# 3.net
KiCad netlist of a schematic drawn in Altium Designer
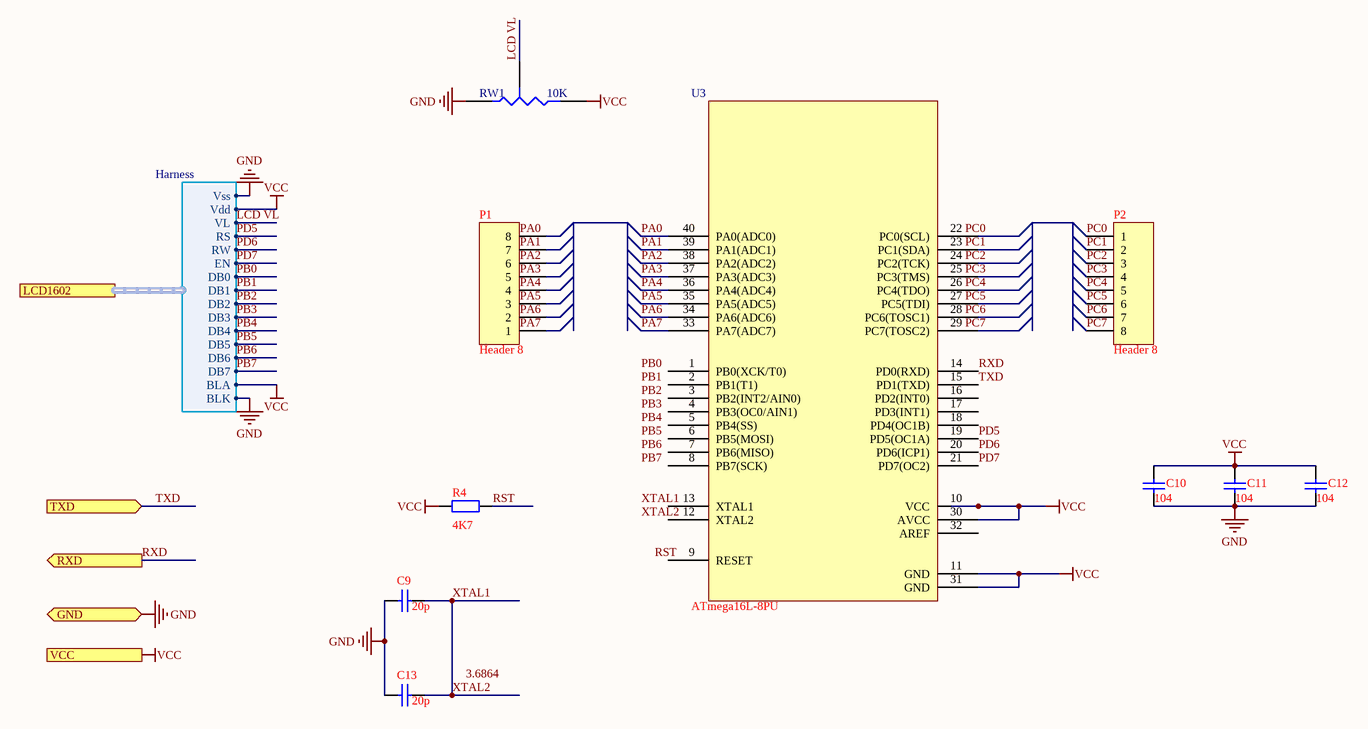
[diagram p0: 3.SchDoc]

(export (version "E")
  (design (tool "Eeschema 10.0.6"))
  (components
    (comp (ref "*") (value "ATmega16L-8PU") (libsource (lib "altium-import") (part "root_0_ATmega16L-8PU_")))
    (comp (ref "C9")
      (value "20p")
      (footprint "0402")
      (description "Capacitor (Semiconductor SIM Model)")
      (fields (field (name "Comment") "Cap Semi") (field (name "PUBLISHER") "Altium Limited"))
      (libsource (lib "Miscellaneous Devices") (part "Cap Semi"))
    )
    (comp (ref "C10")
      (value "104")
      (footprint "0402")
      (description "Capacitor (Semiconductor SIM Model)")
      (fields (field (name "Comment") "Cap Semi") (field (name "PUBLISHER") "Altium Limited"))
      (libsource (lib "Miscellaneous Devices") (part "Cap Semi"))
    )
    (comp (ref "C11")
      (value "104")
      (footprint "0402")
      (description "Capacitor (Semiconductor SIM Model)")
      (fields (field (name "Comment") "Cap Semi") (field (name "PUBLISHER") "Altium Limited"))
      (libsource (lib "Miscellaneous Devices") (part "Cap Semi"))
    )
    (comp (ref "C12")
      (value "104")
      (footprint "0402")
      (description "Capacitor (Semiconductor SIM Model)")
      (fields (field (name "Comment") "Cap Semi") (field (name "PUBLISHER") "Altium Limited"))
      (libsource (lib "Miscellaneous Devices") (part "Cap Semi"))
    )
    (comp (ref "C13")
      (value "20p")
      (footprint "0402")
      (description "Capacitor (Semiconductor SIM Model)")
      (fields (field (name "Comment") "Cap Semi") (field (name "PUBLISHER") "Altium Limited"))
      (libsource (lib "Miscellaneous Devices") (part "Cap Semi"))
    )
    (comp (ref "P1")
      (value "Header 8")
      (footprint "HDR1X8")
      (description "Header, 8-Pin")
      (fields (field (name "PUBLISHER") "Altium Limited"))
      (libsource (lib "") (part "Header 8_1"))
    )
    (comp (ref "P2")
      (value "Header 8")
      (footprint "HDR1X8")
      (description "Header, 8-Pin")
      (fields (field (name "PUBLISHER") "Altium Limited"))
      (libsource (lib "Miscellaneous Connectors") (part "Header 8"))
    )
    (comp (ref "R4")
      (value "4K7")
      (footprint "AXIAL-0.4")
      (description "Resistor")
      (fields (field (name "Comment") "Res2") (field (name "PUBLISHER") "Altium Limited"))
      (libsource (lib "Miscellaneous Devices") (part "Res2"))
    )
    (comp (ref "RW1")
      (value "10K")
      (footprint "VR3")
      (description "Tapped Resistor")
      (fields (field (name "Comment") "Res Tap") (field (name "PUBLISHER") "Altium Limited"))
      (libsource (lib "Miscellaneous Devices") (part "Res Tap"))
    )
    (comp (ref "U3") (value "ATmega16L-8PU") (libsource (lib "Schlib1") (part "ATmega16L-8PU")))
  )
  (nets
    (net (code "3") (name "/LCD VL") (class "Default")
      (node (ref "RW1") (pin "3") (pinfunction "TAP_3") (pintype "passive"))
    )
    (net (code "4") (name "/PA0") (class "Default")
      (node (ref "U3") (pin "40") (pinfunction "PA0(ADC0)_40") (pintype "passive"))
    )
    (net (code "5") (name "/PA1") (class "Default")
      (node (ref "U3") (pin "39") (pinfunction "PA1(ADC1)_39") (pintype "passive"))
    )
    (net (code "6") (name "/PA2") (class "Default")
      (node (ref "U3") (pin "38") (pinfunction "PA2(ADC2)_38") (pintype "passive"))
    )
    (net (code "7") (name "/PA3") (class "Default")
      (node (ref "U3") (pin "37") (pinfunction "PA3(ADC3)_37") (pintype "passive"))
    )
    (net (code "8") (name "/PA4") (class "Default")
      (node (ref "U3") (pin "36") (pinfunction "PA4(ADC4)_36") (pintype "passive"))
    )
    (net (code "9") (name "/PA5") (class "Default")
      (node (ref "U3") (pin "35") (pinfunction "PA5(ADC5)_35") (pintype "passive"))
    )
    (net (code "10") (name "/PA6") (class "Default")
      (node (ref "U3") (pin "34") (pinfunction "PA6(ADC6)_34") (pintype "passive"))
    )
    (net (code "11") (name "/PA7") (class "Default")
      (node (ref "U3") (pin "33") (pinfunction "PA7(ADC7)_33") (pintype "passive"))
    )
    (net (code "20") (name "/PC0") (class "Default")
      (node (ref "P2") (pin "1") (pinfunction "1_1") (pintype "passive"))
    )
    (net (code "21") (name "/PC1") (class "Default")
      (node (ref "P2") (pin "2") (pinfunction "2_2") (pintype "passive"))
    )
    (net (code "22") (name "/PC2") (class "Default")
      (node (ref "P2") (pin "3") (pinfunction "3_3") (pintype "passive"))
    )
    (net (code "23") (name "/PC3") (class "Default")
      (node (ref "P2") (pin "4") (pinfunction "4_4") (pintype "passive"))
    )
    (net (code "24") (name "/PC4") (class "Default")
      (node (ref "P2") (pin "5") (pinfunction "5_5") (pintype "passive"))
    )
    (net (code "25") (name "/PC5") (class "Default")
      (node (ref "P2") (pin "6") (pinfunction "6_6") (pintype "passive"))
    )
    (net (code "26") (name "/PC6") (class "Default")
      (node (ref "P2") (pin "7") (pinfunction "7_7") (pintype "passive"))
    )
    (net (code "27") (name "/PC7") (class "Default")
      (node (ref "P2") (pin "8") (pinfunction "8_8") (pintype "passive"))
    )
    (net (code "28") (name "/PD5") (class "Default")
      (node (ref "U3") (pin "19") (pinfunction "PD5(OC1A)_19") (pintype "passive"))
    )
    (net (code "29") (name "/PD6") (class "Default")
      (node (ref "U3") (pin "20") (pinfunction "PD6(ICP1)_20") (pintype "passive"))
    )
    (net (code "30") (name "/PD7") (class "Default")
      (node (ref "U3") (pin "21") (pinfunction "PD7(OC2)_21") (pintype "passive"))
    )
    (net (code "31") (name "/RST") (class "Default")
      (node (ref "R4") (pin "2") (pinfunction "2_2") (pintype "passive"))
    )
    (net (code "32") (name "/RXD") (class "Default")
      (node (ref "U3") (pin "14") (pinfunction "PD0(RXD)_14") (pintype "passive"))
    )
    (net (code "33") (name "/TXD") (class "Default")
      (node (ref "U3") (pin "15") (pinfunction "PD1(TXD)_15") (pintype "passive"))
    )
    (net (code "34") (name "/XTAL1") (class "Default")
      (node (ref "C13") (pin "2") (pinfunction "2_2") (pintype "passive"))
      (node (ref "C9") (pin "2") (pinfunction "2_2") (pintype "passive"))
    )
    (net (code "36") (name "GND") (class "Default")
      (node (ref "C10") (pin "2") (pinfunction "2_2") (pintype "passive"))
      (node (ref "C11") (pin "1") (pinfunction "1_1") (pintype "passive"))
      (node (ref "C12") (pin "1") (pinfunction "1_1") (pintype "passive"))
      (node (ref "C13") (pin "1") (pinfunction "1_1") (pintype "passive"))
      (node (ref "C9") (pin "1") (pinfunction "1_1") (pintype "passive"))
      (node (ref "RW1") (pin "1") (pinfunction "A_1") (pintype "passive"))
    )
    (net (code "37") (name "VCC") (class "Default")
      (node (ref "C10") (pin "1") (pinfunction "1_1") (pintype "passive"))
      (node (ref "C11") (pin "2") (pinfunction "2_2") (pintype "passive"))
      (node (ref "C12") (pin "2") (pinfunction "2_2") (pintype "passive"))
      (node (ref "R4") (pin "1") (pinfunction "1_1") (pintype "passive"))
      (node (ref "RW1") (pin "2") (pinfunction "B_2") (pintype "passive"))
      (node (ref "U3") (pin "10") (pinfunction "VCC_10") (pintype "passive"))
      (node (ref "U3") (pin "11") (pinfunction "GND_11") (pintype "passive"))
      (node (ref "U3") (pin "30") (pinfunction "AVCC_30") (pintype "passive"))
      (node (ref "U3") (pin "31") (pinfunction "GND_31") (pintype "passive"))
    )
    (net (code "38") (name "unconnected-(*-AREF-Pad32)") (class "Default")
      (node (ref "*") (pin "32") (pinfunction "AREF_32") (pintype "passive"))
    )
    (net (code "39") (name "unconnected-(*-AREF-Pad32)_1") (class "Default")
      (node (ref "*") (pin "32") (pinfunction "AREF_32") (pintype "passive"))
    )
    (net (code "40") (name "unconnected-(*-AREF-Pad32)_2") (class "Default")
      (node (ref "*") (pin "32") (pinfunction "AREF_32") (pintype "passive"))
    )
    (net (code "41") (name "unconnected-(*-AREF-Pad32)_3") (class "Default")
      (node (ref "*") (pin "32") (pinfunction "AREF_32") (pintype "passive"))
    )
    (net (code "42") (name "unconnected-(*-AVCC-Pad30)") (class "Default")
      (node (ref "*") (pin "30") (pinfunction "AVCC_30") (pintype "passive"))
    )
    (net (code "43") (name "unconnected-(*-AVCC-Pad30)_1") (class "Default")
      (node (ref "*") (pin "30") (pinfunction "AVCC_30") (pintype "passive"))
    )
    (net (code "44") (name "unconnected-(*-AVCC-Pad30)_2") (class "Default")
      (node (ref "*") (pin "30") (pinfunction "AVCC_30") (pintype "passive"))
    )
    (net (code "45") (name "unconnected-(*-AVCC-Pad30)_3") (class "Default")
      (node (ref "*") (pin "30") (pinfunction "AVCC_30") (pintype "passive"))
    )
    (net (code "46") (name "unconnected-(*-GND-Pad11)") (class "Default")
      (node (ref "*") (pin "11") (pinfunction "GND_11") (pintype "passive"))
    )
    (net (code "47") (name "unconnected-(*-GND-Pad11)_1") (class "Default")
      (node (ref "*") (pin "11") (pinfunction "GND_11") (pintype "passive"))
    )
    (net (code "48") (name "unconnected-(*-GND-Pad11)_2") (class "Default")
      (node (ref "*") (pin "11") (pinfunction "GND_11") (pintype "passive"))
    )
    (net (code "49") (name "unconnected-(*-GND-Pad11)_3") (class "Default")
      (node (ref "*") (pin "11") (pinfunction "GND_11") (pintype "passive"))
    )
    (net (code "50") (name "unconnected-(*-GND-Pad31)") (class "Default")
      (node (ref "*") (pin "31") (pinfunction "GND_31") (pintype "passive"))
    )
    (net (code "51") (name "unconnected-(*-GND-Pad31)_1") (class "Default")
      (node (ref "*") (pin "31") (pinfunction "GND_31") (pintype "passive"))
    )
    (net (code "52") (name "unconnected-(*-GND-Pad31)_2") (class "Default")
      (node (ref "*") (pin "31") (pinfunction "GND_31") (pintype "passive"))
    )
    (net (code "53") (name "unconnected-(*-GND-Pad31)_3") (class "Default")
      (node (ref "*") (pin "31") (pinfunction "GND_31") (pintype "passive"))
    )
    (net (code "54") (name "unconnected-(*-PA0(ADC0)-Pad40)") (class "Default")
      (node (ref "*") (pin "40") (pinfunction "PA0(ADC0)_40") (pintype "passive"))
    )
    (net (code "55") (name "unconnected-(*-PA0(ADC0)-Pad40)_1") (class "Default")
      (node (ref "*") (pin "40") (pinfunction "PA0(ADC0)_40") (pintype "passive"))
    )
    (net (code "56") (name "unconnected-(*-PA0(ADC0)-Pad40)_2") (class "Default")
      (node (ref "*") (pin "40") (pinfunction "PA0(ADC0)_40") (pintype "passive"))
    )
    (net (code "57") (name "unconnected-(*-PA0(ADC0)-Pad40)_3") (class "Default")
      (node (ref "*") (pin "40") (pinfunction "PA0(ADC0)_40") (pintype "passive"))
    )
    (net (code "58") (name "unconnected-(*-PA1(ADC1)-Pad39)") (class "Default")
      (node (ref "*") (pin "39") (pinfunction "PA1(ADC1)_39") (pintype "passive"))
    )
    (net (code "59") (name "unconnected-(*-PA1(ADC1)-Pad39)_1") (class "Default")
      (node (ref "*") (pin "39") (pinfunction "PA1(ADC1)_39") (pintype "passive"))
    )
    (net (code "60") (name "unconnected-(*-PA1(ADC1)-Pad39)_2") (class "Default")
      (node (ref "*") (pin "39") (pinfunction "PA1(ADC1)_39") (pintype "passive"))
    )
    (net (code "61") (name "unconnected-(*-PA1(ADC1)-Pad39)_3") (class "Default")
      (node (ref "*") (pin "39") (pinfunction "PA1(ADC1)_39") (pintype "passive"))
    )
    (net (code "62") (name "unconnected-(*-PA2(ADC2)-Pad38)") (class "Default")
      (node (ref "*") (pin "38") (pinfunction "PA2(ADC2)_38") (pintype "passive"))
    )
    (net (code "63") (name "unconnected-(*-PA2(ADC2)-Pad38)_1") (class "Default")
      (node (ref "*") (pin "38") (pinfunction "PA2(ADC2)_38") (pintype "passive"))
    )
    (net (code "64") (name "unconnected-(*-PA2(ADC2)-Pad38)_2") (class "Default")
      (node (ref "*") (pin "38") (pinfunction "PA2(ADC2)_38") (pintype "passive"))
    )
    (net (code "65") (name "unconnected-(*-PA2(ADC2)-Pad38)_3") (class "Default")
      (node (ref "*") (pin "38") (pinfunction "PA2(ADC2)_38") (pintype "passive"))
    )
    (net (code "66") (name "unconnected-(*-PA3(ADC3)-Pad37)") (class "Default")
      (node (ref "*") (pin "37") (pinfunction "PA3(ADC3)_37") (pintype "passive"))
    )
    (net (code "67") (name "unconnected-(*-PA3(ADC3)-Pad37)_1") (class "Default")
      (node (ref "*") (pin "37") (pinfunction "PA3(ADC3)_37") (pintype "passive"))
    )
    (net (code "68") (name "unconnected-(*-PA3(ADC3)-Pad37)_2") (class "Default")
      (node (ref "*") (pin "37") (pinfunction "PA3(ADC3)_37") (pintype "passive"))
    )
    (net (code "69") (name "unconnected-(*-PA3(ADC3)-Pad37)_3") (class "Default")
      (node (ref "*") (pin "37") (pinfunction "PA3(ADC3)_37") (pintype "passive"))
    )
    (net (code "70") (name "unconnected-(*-PA4(ADC4)-Pad36)") (class "Default")
      (node (ref "*") (pin "36") (pinfunction "PA4(ADC4)_36") (pintype "passive"))
    )
    (net (code "71") (name "unconnected-(*-PA4(ADC4)-Pad36)_1") (class "Default")
      (node (ref "*") (pin "36") (pinfunction "PA4(ADC4)_36") (pintype "passive"))
    )
    (net (code "72") (name "unconnected-(*-PA4(ADC4)-Pad36)_2") (class "Default")
      (node (ref "*") (pin "36") (pinfunction "PA4(ADC4)_36") (pintype "passive"))
    )
    (net (code "73") (name "unconnected-(*-PA4(ADC4)-Pad36)_3") (class "Default")
      (node (ref "*") (pin "36") (pinfunction "PA4(ADC4)_36") (pintype "passive"))
    )
    (net (code "74") (name "unconnected-(*-PA5(ADC5)-Pad35)") (class "Default")
      (node (ref "*") (pin "35") (pinfunction "PA5(ADC5)_35") (pintype "passive"))
    )
    (net (code "75") (name "unconnected-(*-PA5(ADC5)-Pad35)_1") (class "Default")
      (node (ref "*") (pin "35") (pinfunction "PA5(ADC5)_35") (pintype "passive"))
    )
    (net (code "76") (name "unconnected-(*-PA5(ADC5)-Pad35)_2") (class "Default")
      (node (ref "*") (pin "35") (pinfunction "PA5(ADC5)_35") (pintype "passive"))
    )
    (net (code "77") (name "unconnected-(*-PA5(ADC5)-Pad35)_3") (class "Default")
      (node (ref "*") (pin "35") (pinfunction "PA5(ADC5)_35") (pintype "passive"))
    )
    (net (code "78") (name "unconnected-(*-PA6(ADC6)-Pad34)") (class "Default")
      (node (ref "*") (pin "34") (pinfunction "PA6(ADC6)_34") (pintype "passive"))
    )
    (net (code "79") (name "unconnected-(*-PA6(ADC6)-Pad34)_1") (class "Default")
      (node (ref "*") (pin "34") (pinfunction "PA6(ADC6)_34") (pintype "passive"))
    )
    (net (code "80") (name "unconnected-(*-PA6(ADC6)-Pad34)_2") (class "Default")
      (node (ref "*") (pin "34") (pinfunction "PA6(ADC6)_34") (pintype "passive"))
    )
    (net (code "81") (name "unconnected-(*-PA6(ADC6)-Pad34)_3") (class "Default")
      (node (ref "*") (pin "34") (pinfunction "PA6(ADC6)_34") (pintype "passive"))
    )
    (net (code "82") (name "unconnected-(*-PA7(ADC7)-Pad33)") (class "Default")
      (node (ref "*") (pin "33") (pinfunction "PA7(ADC7)_33") (pintype "passive"))
    )
    (net (code "83") (name "unconnected-(*-PA7(ADC7)-Pad33)_1") (class "Default")
      (node (ref "*") (pin "33") (pinfunction "PA7(ADC7)_33") (pintype "passive"))
    )
    (net (code "84") (name "unconnected-(*-PA7(ADC7)-Pad33)_2") (class "Default")
      (node (ref "*") (pin "33") (pinfunction "PA7(ADC7)_33") (pintype "passive"))
    )
    (net (code "85") (name "unconnected-(*-PA7(ADC7)-Pad33)_3") (class "Default")
      (node (ref "*") (pin "33") (pinfunction "PA7(ADC7)_33") (pintype "passive"))
    )
    (net (code "86") (name "unconnected-(*-PB0(XCK{slash}T0)-Pad1)") (class "Default")
      (node (ref "*") (pin "1") (pinfunction "PB0(XCK/T0)_1") (pintype "passive"))
    )
    (net (code "87") (name "unconnected-(*-PB0(XCK{slash}T0)-Pad1)_1") (class "Default")
      (node (ref "*") (pin "1") (pinfunction "PB0(XCK/T0)_1") (pintype "passive"))
    )
    (net (code "88") (name "unconnected-(*-PB0(XCK{slash}T0)-Pad1)_2") (class "Default")
      (node (ref "*") (pin "1") (pinfunction "PB0(XCK/T0)_1") (pintype "passive"))
    )
    (net (code "89") (name "unconnected-(*-PB0(XCK{slash}T0)-Pad1)_3") (class "Default")
      (node (ref "*") (pin "1") (pinfunction "PB0(XCK/T0)_1") (pintype "passive"))
    )
    (net (code "90") (name "unconnected-(*-PB1(T1)-Pad2)") (class "Default")
      (node (ref "*") (pin "2") (pinfunction "PB1(T1)_2") (pintype "passive"))
    )
    (net (code "91") (name "unconnected-(*-PB1(T1)-Pad2)_1") (class "Default")
      (node (ref "*") (pin "2") (pinfunction "PB1(T1)_2") (pintype "passive"))
    )
    (net (code "92") (name "unconnected-(*-PB1(T1)-Pad2)_2") (class "Default")
      (node (ref "*") (pin "2") (pinfunction "PB1(T1)_2") (pintype "passive"))
    )
    (net (code "93") (name "unconnected-(*-PB1(T1)-Pad2)_3") (class "Default")
      (node (ref "*") (pin "2") (pinfunction "PB1(T1)_2") (pintype "passive"))
    )
    (net (code "94") (name "unconnected-(*-PB2(INT2{slash}AIN0)-Pad3)") (class "Default")
      (node (ref "*") (pin "3") (pinfunction "PB2(INT2/AIN0)_3") (pintype "passive"))
    )
    (net (code "95") (name "unconnected-(*-PB2(INT2{slash}AIN0)-Pad3)_1") (class "Default")
      (node (ref "*") (pin "3") (pinfunction "PB2(INT2/AIN0)_3") (pintype "passive"))
    )
    (net (code "96") (name "unconnected-(*-PB2(INT2{slash}AIN0)-Pad3)_2") (class "Default")
      (node (ref "*") (pin "3") (pinfunction "PB2(INT2/AIN0)_3") (pintype "passive"))
    )
    (net (code "97") (name "unconnected-(*-PB2(INT2{slash}AIN0)-Pad3)_3") (class "Default")
      (node (ref "*") (pin "3") (pinfunction "PB2(INT2/AIN0)_3") (pintype "passive"))
    )
    (net (code "98") (name "unconnected-(*-PB3(OC0{slash}AIN1)-Pad4)") (class "Default")
      (node (ref "*") (pin "4") (pinfunction "PB3(OC0/AIN1)_4") (pintype "passive"))
    )
    (net (code "99") (name "unconnected-(*-PB3(OC0{slash}AIN1)-Pad4)_1") (class "Default")
      (node (ref "*") (pin "4") (pinfunction "PB3(OC0/AIN1)_4") (pintype "passive"))
    )
    (net (code "100") (name "unconnected-(*-PB3(OC0{slash}AIN1)-Pad4)_2") (class "Default")
      (node (ref "*") (pin "4") (pinfunction "PB3(OC0/AIN1)_4") (pintype "passive"))
    )
    (net (code "101") (name "unconnected-(*-PB3(OC0{slash}AIN1)-Pad4)_3") (class "Default")
      (node (ref "*") (pin "4") (pinfunction "PB3(OC0/AIN1)_4") (pintype "passive"))
    )
    (net (code "102") (name "unconnected-(*-PB4(SS)-Pad5)") (class "Default")
      (node (ref "*") (pin "5") (pinfunction "PB4(SS)_5") (pintype "passive"))
    )
    (net (code "103") (name "unconnected-(*-PB4(SS)-Pad5)_1") (class "Default")
      (node (ref "*") (pin "5") (pinfunction "PB4(SS)_5") (pintype "passive"))
    )
    (net (code "104") (name "unconnected-(*-PB4(SS)-Pad5)_2") (class "Default")
      (node (ref "*") (pin "5") (pinfunction "PB4(SS)_5") (pintype "passive"))
    )
    (net (code "105") (name "unconnected-(*-PB4(SS)-Pad5)_3") (class "Default")
      (node (ref "*") (pin "5") (pinfunction "PB4(SS)_5") (pintype "passive"))
    )
    (net (code "106") (name "unconnected-(*-PB5(MOSI)-Pad6)") (class "Default")
      (node (ref "*") (pin "6") (pinfunction "PB5(MOSI)_6") (pintype "passive"))
    )
    (net (code "107") (name "unconnected-(*-PB5(MOSI)-Pad6)_1") (class "Default")
      (node (ref "*") (pin "6") (pinfunction "PB5(MOSI)_6") (pintype "passive"))
    )
    (net (code "108") (name "unconnected-(*-PB5(MOSI)-Pad6)_2") (class "Default")
      (node (ref "*") (pin "6") (pinfunction "PB5(MOSI)_6") (pintype "passive"))
    )
    (net (code "109") (name "unconnected-(*-PB5(MOSI)-Pad6)_3") (class "Default")
      (node (ref "*") (pin "6") (pinfunction "PB5(MOSI)_6") (pintype "passive"))
    )
    (net (code "110") (name "unconnected-(*-PB6(MISO)-Pad7)") (class "Default")
      (node (ref "*") (pin "7") (pinfunction "PB6(MISO)_7") (pintype "passive"))
    )
    (net (code "111") (name "unconnected-(*-PB6(MISO)-Pad7)_1") (class "Default")
      (node (ref "*") (pin "7") (pinfunction "PB6(MISO)_7") (pintype "passive"))
    )
    (net (code "112") (name "unconnected-(*-PB6(MISO)-Pad7)_2") (class "Default")
      (node (ref "*") (pin "7") (pinfunction "PB6(MISO)_7") (pintype "passive"))
    )
    (net (code "113") (name "unconnected-(*-PB6(MISO)-Pad7)_3") (class "Default")
      (node (ref "*") (pin "7") (pinfunction "PB6(MISO)_7") (pintype "passive"))
    )
    (net (code "114") (name "unconnected-(*-PB7(SCK)-Pad8)") (class "Default")
      (node (ref "*") (pin "8") (pinfunction "PB7(SCK)_8") (pintype "passive"))
    )
    (net (code "115") (name "unconnected-(*-PB7(SCK)-Pad8)_1") (class "Default")
      (node (ref "*") (pin "8") (pinfunction "PB7(SCK)_8") (pintype "passive"))
    )
    (net (code "116") (name "unconnected-(*-PB7(SCK)-Pad8)_2") (class "Default")
      (node (ref "*") (pin "8") (pinfunction "PB7(SCK)_8") (pintype "passive"))
    )
    (net (code "117") (name "unconnected-(*-PB7(SCK)-Pad8)_3") (class "Default")
      (node (ref "*") (pin "8") (pinfunction "PB7(SCK)_8") (pintype "passive"))
    )
    (net (code "118") (name "unconnected-(*-PC0(SCL)-Pad22)") (class "Default")
      (node (ref "*") (pin "22") (pinfunction "PC0(SCL)_22") (pintype "passive"))
    )
    (net (code "119") (name "unconnected-(*-PC0(SCL)-Pad22)_1") (class "Default")
      (node (ref "*") (pin "22") (pinfunction "PC0(SCL)_22") (pintype "passive"))
    )
    (net (code "120") (name "unconnected-(*-PC0(SCL)-Pad22)_2") (class "Default")
      (node (ref "*") (pin "22") (pinfunction "PC0(SCL)_22") (pintype "passive"))
    )
    (net (code "121") (name "unconnected-(*-PC0(SCL)-Pad22)_3") (class "Default")
      (node (ref "*") (pin "22") (pinfunction "PC0(SCL)_22") (pintype "passive"))
    )
    (net (code "122") (name "unconnected-(*-PC1(SDA)-Pad23)") (class "Default")
      (node (ref "*") (pin "23") (pinfunction "PC1(SDA)_23") (pintype "passive"))
    )
    (net (code "123") (name "unconnected-(*-PC1(SDA)-Pad23)_1") (class "Default")
      (node (ref "*") (pin "23") (pinfunction "PC1(SDA)_23") (pintype "passive"))
    )
    (net (code "124") (name "unconnected-(*-PC1(SDA)-Pad23)_2") (class "Default")
      (node (ref "*") (pin "23") (pinfunction "PC1(SDA)_23") (pintype "passive"))
    )
    (net (code "125") (name "unconnected-(*-PC1(SDA)-Pad23)_3") (class "Default")
      (node (ref "*") (pin "23") (pinfunction "PC1(SDA)_23") (pintype "passive"))
    )
    (net (code "126") (name "unconnected-(*-PC2(TCK)-Pad24)") (class "Default")
      (node (ref "*") (pin "24") (pinfunction "PC2(TCK)_24") (pintype "passive"))
    )
    (net (code "127") (name "unconnected-(*-PC2(TCK)-Pad24)_1") (class "Default")
      (node (ref "*") (pin "24") (pinfunction "PC2(TCK)_24") (pintype "passive"))
    )
    (net (code "128") (name "unconnected-(*-PC2(TCK)-Pad24)_2") (class "Default")
      (node (ref "*") (pin "24") (pinfunction "PC2(TCK)_24") (pintype "passive"))
    )
    (net (code "129") (name "unconnected-(*-PC2(TCK)-Pad24)_3") (class "Default")
      (node (ref "*") (pin "24") (pinfunction "PC2(TCK)_24") (pintype "passive"))
    )
    (net (code "130") (name "unconnected-(*-PC3(TMS)-Pad25)") (class "Default")
      (node (ref "*") (pin "25") (pinfunction "PC3(TMS)_25") (pintype "passive"))
    )
    (net (code "131") (name "unconnected-(*-PC3(TMS)-Pad25)_1") (class "Default")
      (node (ref "*") (pin "25") (pinfunction "PC3(TMS)_25") (pintype "passive"))
    )
    (net (code "132") (name "unconnected-(*-PC3(TMS)-Pad25)_2") (class "Default")
      (node (ref "*") (pin "25") (pinfunction "PC3(TMS)_25") (pintype "passive"))
    )
    (net (code "133") (name "unconnected-(*-PC3(TMS)-Pad25)_3") (class "Default")
      (node (ref "*") (pin "25") (pinfunction "PC3(TMS)_25") (pintype "passive"))
    )
    (net (code "134") (name "unconnected-(*-PC4(TDO)-Pad26)") (class "Default")
      (node (ref "*") (pin "26") (pinfunction "PC4(TDO)_26") (pintype "passive"))
    )
    (net (code "135") (name "unconnected-(*-PC4(TDO)-Pad26)_1") (class "Default")
      (node (ref "*") (pin "26") (pinfunction "PC4(TDO)_26") (pintype "passive"))
    )
    (net (code "136") (name "unconnected-(*-PC4(TDO)-Pad26)_2") (class "Default")
      (node (ref "*") (pin "26") (pinfunction "PC4(TDO)_26") (pintype "passive"))
    )
    (net (code "137") (name "unconnected-(*-PC4(TDO)-Pad26)_3") (class "Default")
      (node (ref "*") (pin "26") (pinfunction "PC4(TDO)_26") (pintype "passive"))
    )
    (net (code "138") (name "unconnected-(*-PC5(TDI)-Pad27)") (class "Default")
      (node (ref "*") (pin "27") (pinfunction "PC5(TDI)_27") (pintype "passive"))
    )
    (net (code "139") (name "unconnected-(*-PC5(TDI)-Pad27)_1") (class "Default")
      (node (ref "*") (pin "27") (pinfunction "PC5(TDI)_27") (pintype "passive"))
    )
    (net (code "140") (name "unconnected-(*-PC5(TDI)-Pad27)_2") (class "Default")
      (node (ref "*") (pin "27") (pinfunction "PC5(TDI)_27") (pintype "passive"))
    )
    (net (code "141") (name "unconnected-(*-PC5(TDI)-Pad27)_3") (class "Default")
      (node (ref "*") (pin "27") (pinfunction "PC5(TDI)_27") (pintype "passive"))
    )
    (net (code "142") (name "unconnected-(*-PC6(TOSC1)-Pad28)") (class "Default")
      (node (ref "*") (pin "28") (pinfunction "PC6(TOSC1)_28") (pintype "passive"))
    )
    (net (code "143") (name "unconnected-(*-PC6(TOSC1)-Pad28)_1") (class "Default")
      (node (ref "*") (pin "28") (pinfunction "PC6(TOSC1)_28") (pintype "passive"))
    )
    (net (code "144") (name "unconnected-(*-PC6(TOSC1)-Pad28)_2") (class "Default")
      (node (ref "*") (pin "28") (pinfunction "PC6(TOSC1)_28") (pintype "passive"))
    )
    (net (code "145") (name "unconnected-(*-PC6(TOSC1)-Pad28)_3") (class "Default")
      (node (ref "*") (pin "28") (pinfunction "PC6(TOSC1)_28") (pintype "passive"))
    )
    (net (code "146") (name "unconnected-(*-PC7(TOSC2)-Pad29)") (class "Default")
      (node (ref "*") (pin "29") (pinfunction "PC7(TOSC2)_29") (pintype "passive"))
    )
    (net (code "147") (name "unconnected-(*-PC7(TOSC2)-Pad29)_1") (class "Default")
      (node (ref "*") (pin "29") (pinfunction "PC7(TOSC2)_29") (pintype "passive"))
    )
    (net (code "148") (name "unconnected-(*-PC7(TOSC2)-Pad29)_2") (class "Default")
      (node (ref "*") (pin "29") (pinfunction "PC7(TOSC2)_29") (pintype "passive"))
    )
    (net (code "149") (name "unconnected-(*-PC7(TOSC2)-Pad29)_3") (class "Default")
      (node (ref "*") (pin "29") (pinfunction "PC7(TOSC2)_29") (pintype "passive"))
    )
    (net (code "150") (name "unconnected-(*-PD0(RXD)-Pad14)") (class "Default")
      (node (ref "*") (pin "14") (pinfunction "PD0(RXD)_14") (pintype "passive"))
    )
    (net (code "151") (name "unconnected-(*-PD0(RXD)-Pad14)_1") (class "Default")
      (node (ref "*") (pin "14") (pinfunction "PD0(RXD)_14") (pintype "passive"))
    )
    (net (code "152") (name "unconnected-(*-PD0(RXD)-Pad14)_2") (class "Default")
      (node (ref "*") (pin "14") (pinfunction "PD0(RXD)_14") (pintype "passive"))
    )
    (net (code "153") (name "unconnected-(*-PD0(RXD)-Pad14)_3") (class "Default")
      (node (ref "*") (pin "14") (pinfunction "PD0(RXD)_14") (pintype "passive"))
    )
    (net (code "154") (name "unconnected-(*-PD1(TXD)-Pad15)") (class "Default")
      (node (ref "*") (pin "15") (pinfunction "PD1(TXD)_15") (pintype "passive"))
    )
    (net (code "155") (name "unconnected-(*-PD1(TXD)-Pad15)_1") (class "Default")
      (node (ref "*") (pin "15") (pinfunction "PD1(TXD)_15") (pintype "passive"))
    )
    (net (code "156") (name "unconnected-(*-PD1(TXD)-Pad15)_2") (class "Default")
      (node (ref "*") (pin "15") (pinfunction "PD1(TXD)_15") (pintype "passive"))
    )
    (net (code "157") (name "unconnected-(*-PD1(TXD)-Pad15)_3") (class "Default")
      (node (ref "*") (pin "15") (pinfunction "PD1(TXD)_15") (pintype "passive"))
    )
    (net (code "158") (name "unconnected-(*-PD2(INT0)-Pad16)") (class "Default")
      (node (ref "*") (pin "16") (pinfunction "PD2(INT0)_16") (pintype "passive"))
    )
    (net (code "159") (name "unconnected-(*-PD2(INT0)-Pad16)_1") (class "Default")
      (node (ref "*") (pin "16") (pinfunction "PD2(INT0)_16") (pintype "passive"))
    )
    (net (code "160") (name "unconnected-(*-PD2(INT0)-Pad16)_2") (class "Default")
      (node (ref "*") (pin "16") (pinfunction "PD2(INT0)_16") (pintype "passive"))
    )
    (net (code "161") (name "unconnected-(*-PD2(INT0)-Pad16)_3") (class "Default")
      (node (ref "*") (pin "16") (pinfunction "PD2(INT0)_16") (pintype "passive"))
    )
    (net (code "162") (name "unconnected-(*-PD3(INT1)-Pad17)") (class "Default")
      (node (ref "*") (pin "17") (pinfunction "PD3(INT1)_17") (pintype "passive"))
    )
    (net (code "163") (name "unconnected-(*-PD3(INT1)-Pad17)_1") (class "Default")
      (node (ref "*") (pin "17") (pinfunction "PD3(INT1)_17") (pintype "passive"))
    )
    (net (code "164") (name "unconnected-(*-PD3(INT1)-Pad17)_2") (class "Default")
      (node (ref "*") (pin "17") (pinfunction "PD3(INT1)_17") (pintype "passive"))
    )
    (net (code "165") (name "unconnected-(*-PD3(INT1)-Pad17)_3") (class "Default")
      (node (ref "*") (pin "17") (pinfunction "PD3(INT1)_17") (pintype "passive"))
    )
    (net (code "166") (name "unconnected-(*-PD4(OC1B)-Pad18)") (class "Default")
      (node (ref "*") (pin "18") (pinfunction "PD4(OC1B)_18") (pintype "passive"))
    )
    (net (code "167") (name "unconnected-(*-PD4(OC1B)-Pad18)_1") (class "Default")
      (node (ref "*") (pin "18") (pinfunction "PD4(OC1B)_18") (pintype "passive"))
    )
    (net (code "168") (name "unconnected-(*-PD4(OC1B)-Pad18)_2") (class "Default")
      (node (ref "*") (pin "18") (pinfunction "PD4(OC1B)_18") (pintype "passive"))
    )
    (net (code "169") (name "unconnected-(*-PD4(OC1B)-Pad18)_3") (class "Default")
      (node (ref "*") (pin "18") (pinfunction "PD4(OC1B)_18") (pintype "passive"))
    )
    (net (code "170") (name "unconnected-(*-PD5(OC1A)-Pad19)") (class "Default")
      (node (ref "*") (pin "19") (pinfunction "PD5(OC1A)_19") (pintype "passive"))
    )
    (net (code "171") (name "unconnected-(*-PD5(OC1A)-Pad19)_1") (class "Default")
      (node (ref "*") (pin "19") (pinfunction "PD5(OC1A)_19") (pintype "passive"))
    )
    (net (code "172") (name "unconnected-(*-PD5(OC1A)-Pad19)_2") (class "Default")
      (node (ref "*") (pin "19") (pinfunction "PD5(OC1A)_19") (pintype "passive"))
    )
    (net (code "173") (name "unconnected-(*-PD5(OC1A)-Pad19)_3") (class "Default")
      (node (ref "*") (pin "19") (pinfunction "PD5(OC1A)_19") (pintype "passive"))
    )
    (net (code "174") (name "unconnected-(*-PD6(ICP1)-Pad20)") (class "Default")
      (node (ref "*") (pin "20") (pinfunction "PD6(ICP1)_20") (pintype "passive"))
    )
    (net (code "175") (name "unconnected-(*-PD6(ICP1)-Pad20)_1") (class "Default")
      (node (ref "*") (pin "20") (pinfunction "PD6(ICP1)_20") (pintype "passive"))
    )
    (net (code "176") (name "unconnected-(*-PD6(ICP1)-Pad20)_2") (class "Default")
      (node (ref "*") (pin "20") (pinfunction "PD6(ICP1)_20") (pintype "passive"))
    )
    (net (code "177") (name "unconnected-(*-PD6(ICP1)-Pad20)_3") (class "Default")
      (node (ref "*") (pin "20") (pinfunction "PD6(ICP1)_20") (pintype "passive"))
    )
    (net (code "178") (name "unconnected-(*-PD7(OC2)-Pad21)") (class "Default")
      (node (ref "*") (pin "21") (pinfunction "PD7(OC2)_21") (pintype "passive"))
    )
    (net (code "179") (name "unconnected-(*-PD7(OC2)-Pad21)_1") (class "Default")
      (node (ref "*") (pin "21") (pinfunction "PD7(OC2)_21") (pintype "passive"))
    )
    (net (code "180") (name "unconnected-(*-PD7(OC2)-Pad21)_2") (class "Default")
      (node (ref "*") (pin "21") (pinfunction "PD7(OC2)_21") (pintype "passive"))
    )
    (net (code "181") (name "unconnected-(*-PD7(OC2)-Pad21)_3") (class "Default")
      (node (ref "*") (pin "21") (pinfunction "PD7(OC2)_21") (pintype "passive"))
    )
    (net (code "182") (name "unconnected-(*-RESET-Pad9)") (class "Default")
      (node (ref "*") (pin "9") (pinfunction "RESET_9") (pintype "passive"))
    )
    (net (code "183") (name "unconnected-(*-RESET-Pad9)_1") (class "Default")
      (node (ref "*") (pin "9") (pinfunction "RESET_9") (pintype "passive"))
    )
    (net (code "184") (name "unconnected-(*-RESET-Pad9)_2") (class "Default")
      (node (ref "*") (pin "9") (pinfunction "RESET_9") (pintype "passive"))
    )
    (net (code "185") (name "unconnected-(*-RESET-Pad9)_3") (class "Default")
      (node (ref "*") (pin "9") (pinfunction "RESET_9") (pintype "passive"))
    )
    (net (code "186") (name "unconnected-(*-VCC-Pad10)") (class "Default")
      (node (ref "*") (pin "10") (pinfunction "VCC_10") (pintype "passive"))
    )
    (net (code "187") (name "unconnected-(*-VCC-Pad10)_1") (class "Default")
      (node (ref "*") (pin "10") (pinfunction "VCC_10") (pintype "passive"))
    )
    (net (code "188") (name "unconnected-(*-VCC-Pad10)_2") (class "Default")
      (node (ref "*") (pin "10") (pinfunction "VCC_10") (pintype "passive"))
    )
    (net (code "189") (name "unconnected-(*-VCC-Pad10)_3") (class "Default")
      (node (ref "*") (pin "10") (pinfunction "VCC_10") (pintype "passive"))
    )
    (net (code "190") (name "unconnected-(*-XTAL1-Pad13)") (class "Default")
      (node (ref "*") (pin "13") (pinfunction "XTAL1_13") (pintype "passive"))
    )
    (net (code "191") (name "unconnected-(*-XTAL1-Pad13)_1") (class "Default")
      (node (ref "*") (pin "13") (pinfunction "XTAL1_13") (pintype "passive"))
    )
    (net (code "192") (name "unconnected-(*-XTAL1-Pad13)_2") (class "Default")
      (node (ref "*") (pin "13") (pinfunction "XTAL1_13") (pintype "passive"))
    )
    (net (code "193") (name "unconnected-(*-XTAL1-Pad13)_3") (class "Default")
      (node (ref "*") (pin "13") (pinfunction "XTAL1_13") (pintype "passive"))
    )
    (net (code "194") (name "unconnected-(*-XTAL2-Pad12)") (class "Default")
      (node (ref "*") (pin "12") (pinfunction "XTAL2_12") (pintype "passive"))
    )
    (net (code "195") (name "unconnected-(*-XTAL2-Pad12)_1") (class "Default")
      (node (ref "*") (pin "12") (pinfunction "XTAL2_12") (pintype "passive"))
    )
    (net (code "196") (name "unconnected-(*-XTAL2-Pad12)_2") (class "Default")
      (node (ref "*") (pin "12") (pinfunction "XTAL2_12") (pintype "passive"))
    )
    (net (code "197") (name "unconnected-(*-XTAL2-Pad12)_3") (class "Default")
      (node (ref "*") (pin "12") (pinfunction "XTAL2_12") (pintype "passive"))
    )
    (net (code "198") (name "unconnected-(P1-Pad1)") (class "Default")
      (node (ref "P1") (pin "1") (pinfunction "1_1") (pintype "passive"))
    )
    (net (code "199") (name "unconnected-(P1-Pad2)") (class "Default")
      (node (ref "P1") (pin "2") (pinfunction "2_2") (pintype "passive"))
    )
    (net (code "200") (name "unconnected-(P1-Pad3)") (class "Default")
      (node (ref "P1") (pin "3") (pinfunction "3_3") (pintype "passive"))
    )
    (net (code "201") (name "unconnected-(P1-Pad4)") (class "Default")
      (node (ref "P1") (pin "4") (pinfunction "4_4") (pintype "passive"))
    )
    (net (code "202") (name "unconnected-(P1-Pad5)") (class "Default")
      (node (ref "P1") (pin "5") (pinfunction "5_5") (pintype "passive"))
    )
    (net (code "203") (name "unconnected-(P1-Pad6)") (class "Default")
      (node (ref "P1") (pin "6") (pinfunction "6_6") (pintype "passive"))
    )
    (net (code "204") (name "unconnected-(P1-Pad7)") (class "Default")
      (node (ref "P1") (pin "7") (pinfunction "7_7") (pintype "passive"))
    )
    (net (code "205") (name "unconnected-(P1-Pad8)") (class "Default")
      (node (ref "P1") (pin "8") (pinfunction "8_8") (pintype "passive"))
    )
    (net (code "206") (name "unconnected-(U3-AREF-Pad32)") (class "Default")
      (node (ref "U3") (pin "32") (pinfunction "AREF_32") (pintype "passive"))
    )
    (net (code "207") (name "unconnected-(U3-PB0(XCK{slash}T0)-Pad1)") (class "Default")
      (node (ref "U3") (pin "1") (pinfunction "PB0(XCK/T0)_1") (pintype "passive"))
    )
    (net (code "208") (name "unconnected-(U3-PB1(T1)-Pad2)") (class "Default")
      (node (ref "U3") (pin "2") (pinfunction "PB1(T1)_2") (pintype "passive"))
    )
    (net (code "209") (name "unconnected-(U3-PB2(INT2{slash}AIN0)-Pad3)") (class "Default")
      (node (ref "U3") (pin "3") (pinfunction "PB2(INT2/AIN0)_3") (pintype "passive"))
    )
    (net (code "210") (name "unconnected-(U3-PB3(OC0{slash}AIN1)-Pad4)") (class "Default")
      (node (ref "U3") (pin "4") (pinfunction "PB3(OC0/AIN1)_4") (pintype "passive"))
    )
    (net (code "211") (name "unconnected-(U3-PB4(SS)-Pad5)") (class "Default")
      (node (ref "U3") (pin "5") (pinfunction "PB4(SS)_5") (pintype "passive"))
    )
    (net (code "212") (name "unconnected-(U3-PB5(MOSI)-Pad6)") (class "Default")
      (node (ref "U3") (pin "6") (pinfunction "PB5(MOSI)_6") (pintype "passive"))
    )
    (net (code "213") (name "unconnected-(U3-PB6(MISO)-Pad7)") (class "Default")
      (node (ref "U3") (pin "7") (pinfunction "PB6(MISO)_7") (pintype "passive"))
    )
    (net (code "214") (name "unconnected-(U3-PB7(SCK)-Pad8)") (class "Default")
      (node (ref "U3") (pin "8") (pinfunction "PB7(SCK)_8") (pintype "passive"))
    )
    (net (code "215") (name "unconnected-(U3-PC0(SCL)-Pad22)") (class "Default")
      (node (ref "U3") (pin "22") (pinfunction "PC0(SCL)_22") (pintype "passive"))
    )
    (net (code "216") (name "unconnected-(U3-PC1(SDA)-Pad23)") (class "Default")
      (node (ref "U3") (pin "23") (pinfunction "PC1(SDA)_23") (pintype "passive"))
    )
    (net (code "217") (name "unconnected-(U3-PC2(TCK)-Pad24)") (class "Default")
      (node (ref "U3") (pin "24") (pinfunction "PC2(TCK)_24") (pintype "passive"))
    )
    (net (code "218") (name "unconnected-(U3-PC3(TMS)-Pad25)") (class "Default")
      (node (ref "U3") (pin "25") (pinfunction "PC3(TMS)_25") (pintype "passive"))
    )
    (net (code "219") (name "unconnected-(U3-PC4(TDO)-Pad26)") (class "Default")
      (node (ref "U3") (pin "26") (pinfunction "PC4(TDO)_26") (pintype "passive"))
    )
    (net (code "220") (name "unconnected-(U3-PC5(TDI)-Pad27)") (class "Default")
      (node (ref "U3") (pin "27") (pinfunction "PC5(TDI)_27") (pintype "passive"))
    )
    (net (code "221") (name "unconnected-(U3-PC6(TOSC1)-Pad28)") (class "Default")
      (node (ref "U3") (pin "28") (pinfunction "PC6(TOSC1)_28") (pintype "passive"))
    )
    (net (code "222") (name "unconnected-(U3-PC7(TOSC2)-Pad29)") (class "Default")
      (node (ref "U3") (pin "29") (pinfunction "PC7(TOSC2)_29") (pintype "passive"))
    )
    (net (code "223") (name "unconnected-(U3-PD2(INT0)-Pad16)") (class "Default")
      (node (ref "U3") (pin "16") (pinfunction "PD2(INT0)_16") (pintype "passive"))
    )
    (net (code "224") (name "unconnected-(U3-PD3(INT1)-Pad17)") (class "Default")
      (node (ref "U3") (pin "17") (pinfunction "PD3(INT1)_17") (pintype "passive"))
    )
    (net (code "225") (name "unconnected-(U3-PD4(OC1B)-Pad18)") (class "Default")
      (node (ref "U3") (pin "18") (pinfunction "PD4(OC1B)_18") (pintype "passive"))
    )
    (net (code "226") (name "unconnected-(U3-RESET-Pad9)") (class "Default")
      (node (ref "U3") (pin "9") (pinfunction "RESET_9") (pintype "passive"))
    )
    (net (code "227") (name "unconnected-(U3-XTAL1-Pad13)") (class "Default")
      (node (ref "U3") (pin "13") (pinfunction "XTAL1_13") (pintype "passive"))
    )
    (net (code "228") (name "unconnected-(U3-XTAL2-Pad12)") (class "Default")
      (node (ref "U3") (pin "12") (pinfunction "XTAL2_12") (pintype "passive"))
    )
  )
)
